# Sheet1_PWR_connectors.net
KiCad netlist of a schematic drawn in Altium Designer
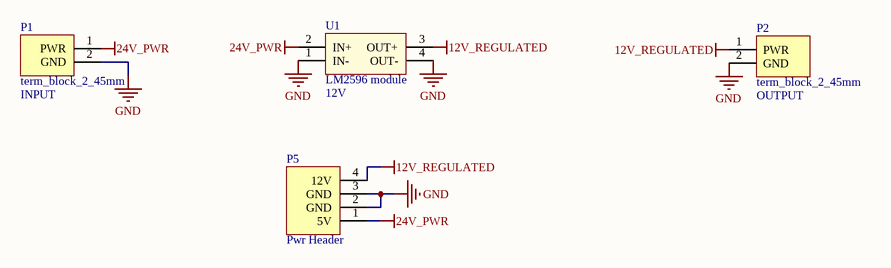
[diagram p0: Sheet1_PWR_connectors.SchDoc]

(export (version "E")
  (design (tool "Eeschema 10.0.6"))
  (components
    (comp (ref "P1")
      (value "term_block_2_45mm")
      (footprint "term_block_2_45mm")
      (description "terminal block, 2.45mm")
      (fields (field (name "DIRECTION") "INPUT"))
      (libsource (lib "") (part "term_block_2_45mm_1"))
    )
    (comp (ref "P2")
      (value "term_block_2_45mm")
      (footprint "term_block_2_45mm")
      (description "terminal block, 2.45mm")
      (fields (field (name "DIRECTION") "OUTPUT"))
      (libsource (lib "SchlibKoruzaExpanderBoard") (part "term_block_2_45mm"))
    )
    (comp (ref "P5")
      (value "Pwr Header")
      (footprint "HDR1X4_CONN")
      (description "1X4 Pwr Header")
      (libsource (lib "SchlibKoruzaExpanderBoard") (part "1x4_pwr_header"))
    )
    (comp (ref "U1")
      (value "LM2596 module")
      (footprint "LM2596 module")
      (fields (field (name "ALTIUM_VALUE") "12V"))
      (libsource (lib "SchlibKoruzaExpanderBoard") (part "LM2596 module"))
    )
  )
  (nets
    (net (code "1") (name "12V_REGULATED") (class "Default")
      (node (ref "P2") (pin "1") (pinfunction "PWR_1") (pintype "passive"))
      (node (ref "P5") (pin "4") (pinfunction "12V_4") (pintype "passive"))
      (node (ref "U1") (pin "3") (pinfunction "OUT+_3") (pintype "passive"))
    )
    (net (code "2") (name "24V_PWR") (class "Default")
      (node (ref "P1") (pin "1") (pinfunction "PWR_1") (pintype "passive"))
      (node (ref "P5") (pin "1") (pinfunction "5V_1") (pintype "passive"))
      (node (ref "U1") (pin "2") (pinfunction "IN+_2") (pintype "passive"))
    )
    (net (code "3") (name "GND") (class "Default")
      (node (ref "P1") (pin "2") (pinfunction "GND_2") (pintype "passive"))
      (node (ref "P2") (pin "2") (pinfunction "GND_2") (pintype "passive"))
      (node (ref "P5") (pin "2") (pinfunction "GND_2") (pintype "passive"))
      (node (ref "P5") (pin "3") (pinfunction "GND_3") (pintype "passive"))
      (node (ref "U1") (pin "1") (pinfunction "IN-_1") (pintype "passive"))
      (node (ref "U1") (pin "4") (pinfunction "OUT-_4") (pintype "passive"))
    )
  )
)
